# Stepper_Control.net
KiCad netlist of a schematic drawn in EasyEDA
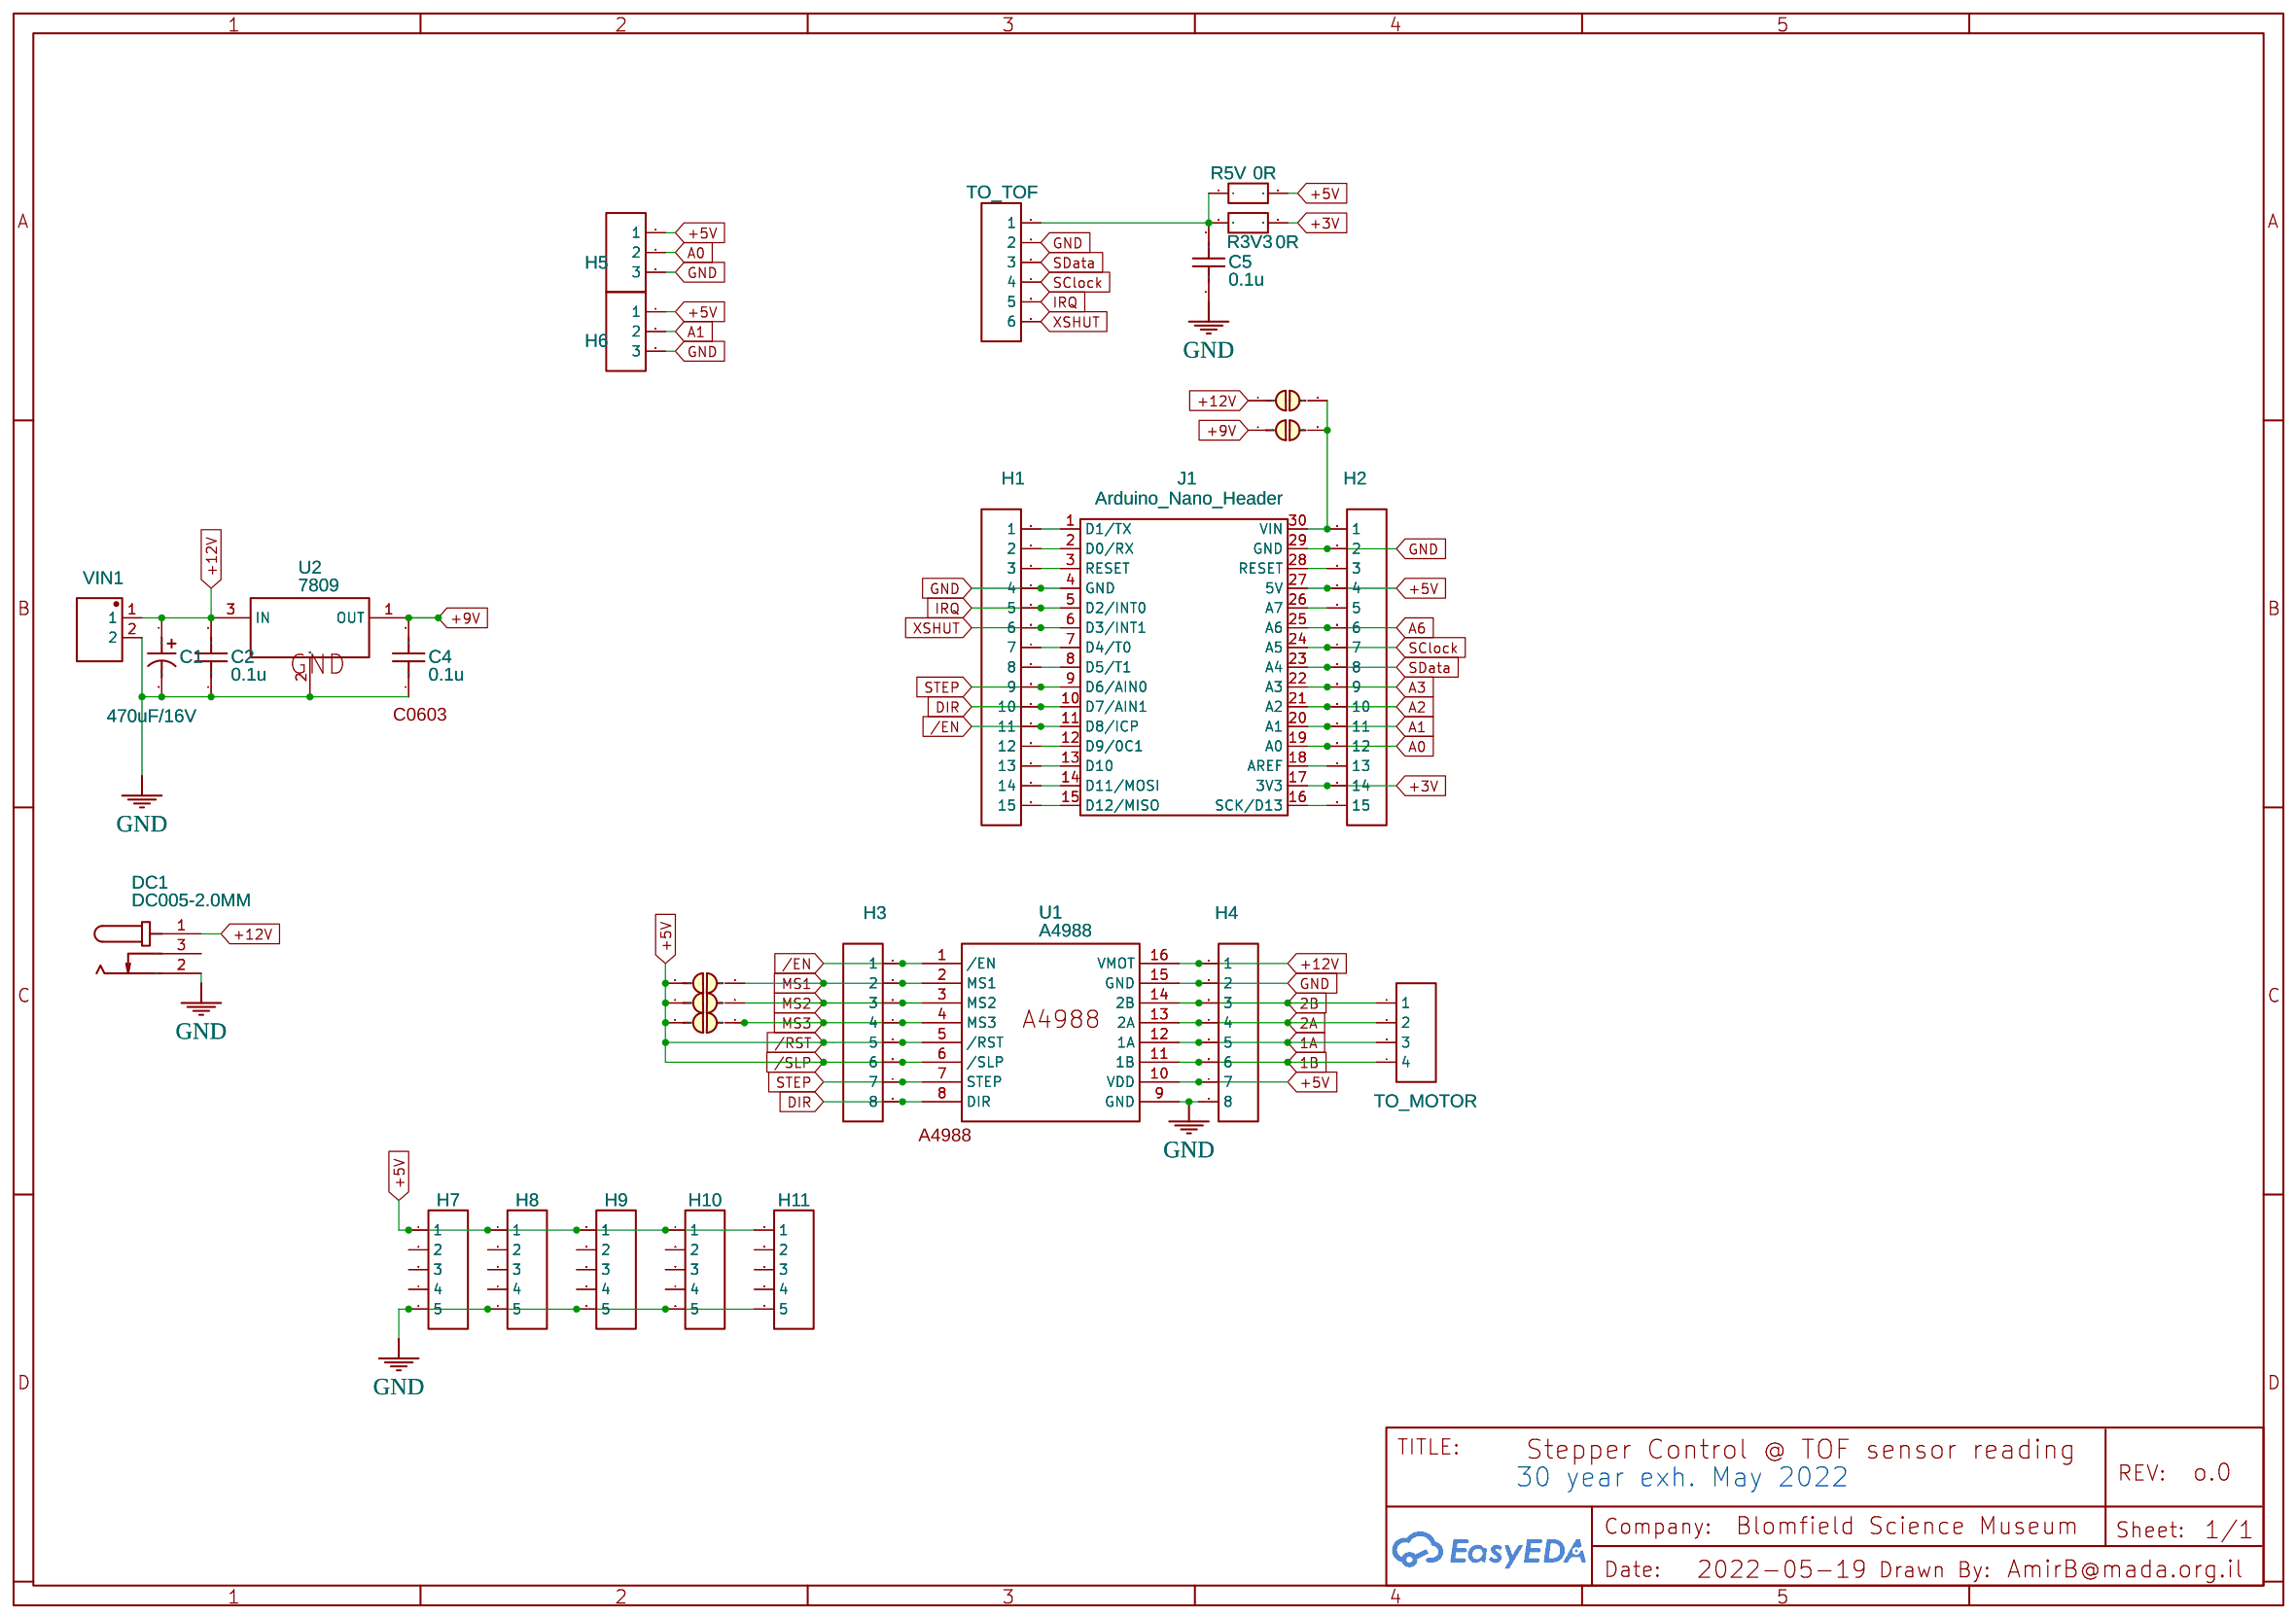
[diagram p0: schematic sheet]

(export (version "E")
  (design (tool "Eeschema 10.0.6"))
  (components
    (comp (ref "C1")
      (value "470uF/16V")
      (fields
        (field (name "BOM_Manufacturer Part") "16V470uF CD110")
        (field (name "BOM_Supplier Part") "C2960230")
      )
      (libsource (lib "") (part "16V470UF CD110"))
    )
    (comp (ref "C2") (value "0.1u") (libsource (lib "") (part "C_0603_US_1")))
    (comp (ref "C4") (value "0.1u") (libsource (lib "") (part "C_0603_US")))
    (comp (ref "C5") (value "0.1u") (libsource (lib "") (part "C_0603_US_1")))
    (comp (ref "DC1")
      (value "DC005-2.0MM")
      (fields (field (name "BOM_Supplier Part") "C111567"))
      (libsource (lib "") (part "DC005-2.0MM"))
    )
    (comp (ref "H1")
      (value "HDR-F-2.54_1x15")
      (fields (field (name "BOM_Supplier Part") "C124408"))
      (libsource (lib "") (part "HDR-F-2.54_1x15_1"))
    )
    (comp (ref "H2")
      (value "HDR-F-2.54_1x15")
      (fields (field (name "BOM_Supplier Part") "C124408"))
      (libsource (lib "") (part "HDR-F-2.54_1x15"))
    )
    (comp (ref "H3")
      (value "HDR-F-2.54_1x8")
      (fields (field (name "BOM_Supplier Part") "C225505"))
      (libsource (lib "") (part "HDR-F-2.54_1x8_1"))
    )
    (comp (ref "H4")
      (value "HDR-F-2.54_1x8")
      (fields (field (name "BOM_Supplier Part") "C225505"))
      (libsource (lib "") (part "HDR-F-2.54_1x8"))
    )
    (comp (ref "H5")
      (value "HDR-F-2.54_1x3")
      (fields (field (name "BOM_Supplier Part") "C146690"))
      (libsource (lib "") (part "HDR-F-2.54_1x3"))
    )
    (comp (ref "H6")
      (value "HDR-F-2.54_1x3")
      (fields (field (name "BOM_Supplier Part") "C146690"))
      (libsource (lib "") (part "HDR-F-2.54_1x3"))
    )
    (comp (ref "H7")
      (value "HDR-F-2.54_1x5")
      (fields (field (name "BOM_Supplier Part") "C50950"))
      (libsource (lib "") (part "HDR-F-2.54_1x5"))
    )
    (comp (ref "H8")
      (value "HDR-F-2.54_1x5")
      (fields (field (name "BOM_Supplier Part") "C50950"))
      (libsource (lib "") (part "HDR-F-2.54_1x5"))
    )
    (comp (ref "H9")
      (value "HDR-F-2.54_1x5")
      (fields (field (name "BOM_Supplier Part") "C50950"))
      (libsource (lib "") (part "HDR-F-2.54_1x5"))
    )
    (comp (ref "H10")
      (value "HDR-F-2.54_1x5")
      (fields (field (name "BOM_Supplier Part") "C50950"))
      (libsource (lib "") (part "HDR-F-2.54_1x5"))
    )
    (comp (ref "H11")
      (value "HDR-F-2.54_1x5")
      (fields (field (name "BOM_Supplier Part") "C50950"))
      (libsource (lib "") (part "HDR-F-2.54_1x5"))
    )
    (comp (ref "J1") (value "Arduino_Nano_Header") (libsource (lib "") (part "Arduino_Nano_Header")))
    (comp (ref "J9V") (value "JUMPER-SMT_2") (libsource (lib "") (part "JUMPER-SMT_2_2")))
    (comp (ref "J12V") (value "JUMPER-SMT_2") (libsource (lib "") (part "JUMPER-SMT_2_1")))
    (comp (ref "JP1") (value "JUMPER-SMT_2") (libsource (lib "") (part "JUMPER-SMT_2")))
    (comp (ref "JP2") (value "JUMPER-SMT_2") (libsource (lib "") (part "JUMPER-SMT_2")))
    (comp (ref "JP3") (value "JUMPER-SMT_2") (libsource (lib "") (part "JUMPER-SMT_2")))
    (comp (ref "R3V3") (value "0R") (libsource (lib "") (part "R_0603_EU")))
    (comp (ref "R5V") (value "0R") (libsource (lib "") (part "R_0603_EU_1")))
    (comp (ref "TO_MOTOR")
      (value "HDR-F-2.54_1x4")
      (fields (field (name "BOM_Supplier Part") "C225501"))
      (libsource (lib "") (part "HDR-F-2.54_1x4"))
    )
    (comp (ref "TO_TOF")
      (value "HDR-F-2.54_1x6")
      (fields (field (name "BOM_Supplier Part") "C40877"))
      (libsource (lib "") (part "HDR-F-2.54_1x6"))
    )
    (comp (ref "U1") (value "A4988") (libsource (lib "") (part "A4988")))
    (comp (ref "U2")
      (value "7809")
      (fields (field (name "BOM_Manufacturer Part") "CJ78L05") (field (name "BOM_Supplier Part") "C2079"))
      (libsource (lib "") (part "7805(SOT-89)"))
    )
    (comp (ref "VIN1")
      (value "640456-2")
      (fields (field (name "BOM_Supplier Part") "C86502"))
      (libsource (lib "") (part "640456-2"))
    )
  )
  (nets
    (net (code "1") (name "+3V") (class "Default")
      (node (ref "H2") (pin "14") (pinfunction "14_14") (pintype "unspecified"))
      (node (ref "J1") (pin "17") (pinfunction "3V3_17") (pintype "unspecified"))
      (node (ref "R3V3") (pin "2") (pinfunction "2_2") (pintype "unspecified"))
    )
    (net (code "2") (name "+5V") (class "Default")
      (node (ref "H10") (pin "1") (pinfunction "1_1") (pintype "unspecified"))
      (node (ref "H11") (pin "1") (pinfunction "1_1") (pintype "unspecified"))
      (node (ref "H2") (pin "4") (pinfunction "4_4") (pintype "unspecified"))
      (node (ref "H3") (pin "5") (pinfunction "5_5") (pintype "unspecified"))
      (node (ref "H3") (pin "6") (pinfunction "6_6") (pintype "unspecified"))
      (node (ref "H4") (pin "7") (pinfunction "7_7") (pintype "unspecified"))
      (node (ref "H5") (pin "1") (pinfunction "1_1") (pintype "input"))
      (node (ref "H6") (pin "1") (pinfunction "1_1") (pintype "input"))
      (node (ref "H7") (pin "1") (pinfunction "1_1") (pintype "unspecified"))
      (node (ref "H8") (pin "1") (pinfunction "1_1") (pintype "unspecified"))
      (node (ref "H9") (pin "1") (pinfunction "1_1") (pintype "unspecified"))
      (node (ref "J1") (pin "27") (pinfunction "5V_27") (pintype "unspecified"))
      (node (ref "JP1") (pin "1") (pinfunction "1_1") (pintype "bidirectional"))
      (node (ref "JP2") (pin "1") (pinfunction "1_1") (pintype "bidirectional"))
      (node (ref "JP3") (pin "1") (pinfunction "1_1") (pintype "bidirectional"))
      (node (ref "R5V") (pin "2") (pinfunction "2_2") (pintype "unspecified"))
      (node (ref "U1") (pin "10") (pinfunction "VDD_10") (pintype "unspecified"))
      (node (ref "U1") (pin "5") (pinfunction "/RST_5") (pintype "unspecified"))
      (node (ref "U1") (pin "6") (pinfunction "/SLP_6") (pintype "unspecified"))
    )
    (net (code "3") (name "+9V") (class "Default")
      (node (ref "C4") (pin "2") (pinfunction "2_2") (pintype "unspecified"))
      (node (ref "J9V") (pin "1") (pinfunction "1_1") (pintype "bidirectional"))
      (node (ref "U2") (pin "1") (pinfunction "OUT_1") (pintype "passive"))
    )
    (net (code "4") (name "+12V") (class "Default")
      (node (ref "C1") (pin "1") (pinfunction "1_1") (pintype "input"))
      (node (ref "C2") (pin "2") (pinfunction "2_2") (pintype "unspecified"))
      (node (ref "DC1") (pin "1") (pinfunction "1_1") (pintype "unspecified"))
      (node (ref "H4") (pin "1") (pinfunction "1_1") (pintype "unspecified"))
      (node (ref "J12V") (pin "1") (pinfunction "1_1") (pintype "bidirectional"))
      (node (ref "U1") (pin "16") (pinfunction "VMOT_16") (pintype "unspecified"))
      (node (ref "U2") (pin "3") (pinfunction "IN_3") (pintype "passive"))
      (node (ref "VIN1") (pin "1") (pinfunction "1_1") (pintype "unspecified"))
    )
    (net (code "5") (name "1A") (class "Default")
      (node (ref "H4") (pin "5") (pinfunction "5_5") (pintype "unspecified"))
      (node (ref "TO_MOTOR") (pin "3") (pinfunction "3_3") (pintype "unspecified"))
      (node (ref "U1") (pin "12") (pinfunction "1A_12") (pintype "unspecified"))
    )
    (net (code "6") (name "1B") (class "Default")
      (node (ref "H4") (pin "6") (pinfunction "6_6") (pintype "unspecified"))
      (node (ref "TO_MOTOR") (pin "4") (pinfunction "4_4") (pintype "unspecified"))
      (node (ref "U1") (pin "11") (pinfunction "1B_11") (pintype "unspecified"))
    )
    (net (code "7") (name "2A") (class "Default")
      (node (ref "H4") (pin "4") (pinfunction "4_4") (pintype "unspecified"))
      (node (ref "TO_MOTOR") (pin "2") (pinfunction "2_2") (pintype "unspecified"))
      (node (ref "U1") (pin "13") (pinfunction "2A_13") (pintype "unspecified"))
    )
    (net (code "8") (name "2B") (class "Default")
      (node (ref "H4") (pin "3") (pinfunction "3_3") (pintype "unspecified"))
      (node (ref "TO_MOTOR") (pin "1") (pinfunction "1_1") (pintype "unspecified"))
      (node (ref "U1") (pin "14") (pinfunction "2B_14") (pintype "unspecified"))
    )
    (net (code "9") (name "A0") (class "Default")
      (node (ref "H2") (pin "12") (pinfunction "12_12") (pintype "unspecified"))
      (node (ref "H5") (pin "2") (pinfunction "2_2") (pintype "input"))
      (node (ref "J1") (pin "19") (pinfunction "A0_19") (pintype "unspecified"))
    )
    (net (code "10") (name "A1") (class "Default")
      (node (ref "H2") (pin "11") (pinfunction "11_11") (pintype "unspecified"))
      (node (ref "H6") (pin "2") (pinfunction "2_2") (pintype "input"))
      (node (ref "J1") (pin "20") (pinfunction "A1_20") (pintype "unspecified"))
    )
    (net (code "11") (name "A2") (class "Default")
      (node (ref "H2") (pin "10") (pinfunction "10_10") (pintype "unspecified"))
      (node (ref "J1") (pin "21") (pinfunction "A2_21") (pintype "unspecified"))
    )
    (net (code "12") (name "A3") (class "Default")
      (node (ref "H2") (pin "9") (pinfunction "9_9") (pintype "unspecified"))
      (node (ref "J1") (pin "22") (pinfunction "A3_22") (pintype "unspecified"))
    )
    (net (code "13") (name "A6") (class "Default")
      (node (ref "H2") (pin "6") (pinfunction "6_6") (pintype "unspecified"))
      (node (ref "J1") (pin "25") (pinfunction "A6_25") (pintype "unspecified"))
    )
    (net (code "14") (name "DIR") (class "Default")
      (node (ref "H1") (pin "10") (pinfunction "10_10") (pintype "unspecified"))
      (node (ref "H3") (pin "8") (pinfunction "8_8") (pintype "unspecified"))
      (node (ref "J1") (pin "10") (pinfunction "D7/AIN1_10") (pintype "unspecified"))
      (node (ref "U1") (pin "8") (pinfunction "DIR_8") (pintype "unspecified"))
    )
    (net (code "15") (name "GND") (class "Default")
      (node (ref "C1") (pin "2") (pinfunction "2_2") (pintype "input"))
      (node (ref "C2") (pin "1") (pinfunction "1_1") (pintype "unspecified"))
      (node (ref "C4") (pin "1") (pinfunction "1_1") (pintype "unspecified"))
      (node (ref "C5") (pin "1") (pinfunction "1_1") (pintype "unspecified"))
      (node (ref "DC1") (pin "2") (pinfunction "2_2") (pintype "unspecified"))
      (node (ref "H1") (pin "4") (pinfunction "4_4") (pintype "unspecified"))
      (node (ref "H10") (pin "5") (pinfunction "5_5") (pintype "unspecified"))
      (node (ref "H11") (pin "5") (pinfunction "5_5") (pintype "unspecified"))
      (node (ref "H2") (pin "2") (pinfunction "2_2") (pintype "unspecified"))
      (node (ref "H4") (pin "2") (pinfunction "2_2") (pintype "unspecified"))
      (node (ref "H4") (pin "8") (pinfunction "8_8") (pintype "unspecified"))
      (node (ref "H5") (pin "3") (pinfunction "3_3") (pintype "input"))
      (node (ref "H6") (pin "3") (pinfunction "3_3") (pintype "input"))
      (node (ref "H7") (pin "5") (pinfunction "5_5") (pintype "unspecified"))
      (node (ref "H8") (pin "5") (pinfunction "5_5") (pintype "unspecified"))
      (node (ref "H9") (pin "5") (pinfunction "5_5") (pintype "unspecified"))
      (node (ref "J1") (pin "29") (pinfunction "GND_29") (pintype "unspecified"))
      (node (ref "J1") (pin "4") (pinfunction "GND_4") (pintype "unspecified"))
      (node (ref "TO_TOF") (pin "2") (pinfunction "2_2") (pintype "input"))
      (node (ref "U1") (pin "15") (pinfunction "GND_15") (pintype "unspecified"))
      (node (ref "U1") (pin "9") (pinfunction "GND_9") (pintype "unspecified"))
      (node (ref "U2") (pin "2") (pinfunction "GND_2") (pintype "passive"))
      (node (ref "VIN1") (pin "2") (pinfunction "2_2") (pintype "unspecified"))
    )
    (net (code "16") (name "IRQ") (class "Default")
      (node (ref "H1") (pin "5") (pinfunction "5_5") (pintype "unspecified"))
      (node (ref "J1") (pin "5") (pinfunction "D2/INT0_5") (pintype "unspecified"))
      (node (ref "TO_TOF") (pin "5") (pinfunction "5_5") (pintype "input"))
    )
    (net (code "17") (name "MS1") (class "Default")
      (node (ref "H3") (pin "2") (pinfunction "2_2") (pintype "unspecified"))
      (node (ref "JP1") (pin "2") (pinfunction "2_2") (pintype "bidirectional"))
      (node (ref "U1") (pin "2") (pinfunction "MS1_2") (pintype "unspecified"))
    )
    (net (code "18") (name "MS2") (class "Default")
      (node (ref "H3") (pin "3") (pinfunction "3_3") (pintype "unspecified"))
      (node (ref "JP2") (pin "2") (pinfunction "2_2") (pintype "bidirectional"))
      (node (ref "U1") (pin "3") (pinfunction "MS2_3") (pintype "unspecified"))
    )
    (net (code "19") (name "MS3") (class "Default")
      (node (ref "H3") (pin "4") (pinfunction "4_4") (pintype "unspecified"))
      (node (ref "JP3") (pin "2") (pinfunction "2_2") (pintype "bidirectional"))
      (node (ref "U1") (pin "4") (pinfunction "MS3_4") (pintype "unspecified"))
    )
    (net (code "20") (name "Net-(C5-Pad2)") (class "Default")
      (node (ref "C5") (pin "2") (pinfunction "2_2") (pintype "unspecified"))
      (node (ref "R3V3") (pin "1") (pinfunction "1_1") (pintype "unspecified"))
      (node (ref "R5V") (pin "1") (pinfunction "1_1") (pintype "unspecified"))
      (node (ref "TO_TOF") (pin "1") (pinfunction "1_1") (pintype "input"))
    )
    (net (code "21") (name "Net-(H1-Pad3)") (class "Default")
      (node (ref "H1") (pin "3") (pinfunction "3_3") (pintype "unspecified"))
      (node (ref "J1") (pin "3") (pinfunction "RESET_3") (pintype "unspecified"))
    )
    (net (code "22") (name "Net-(H2-Pad3)") (class "Default")
      (node (ref "H2") (pin "3") (pinfunction "3_3") (pintype "unspecified"))
      (node (ref "J1") (pin "28") (pinfunction "RESET_28") (pintype "unspecified"))
    )
    (net (code "23") (name "Net-(J1-A7)") (class "Default")
      (node (ref "H2") (pin "5") (pinfunction "5_5") (pintype "unspecified"))
      (node (ref "J1") (pin "26") (pinfunction "A7_26") (pintype "unspecified"))
    )
    (net (code "24") (name "Net-(J1-AREF)") (class "Default")
      (node (ref "H2") (pin "13") (pinfunction "13_13") (pintype "unspecified"))
      (node (ref "J1") (pin "18") (pinfunction "AREF_18") (pintype "unspecified"))
    )
    (net (code "25") (name "Net-(J1-D0{slash}RX)") (class "Default")
      (node (ref "H1") (pin "2") (pinfunction "2_2") (pintype "unspecified"))
      (node (ref "J1") (pin "2") (pinfunction "D0/RX_2") (pintype "unspecified"))
    )
    (net (code "26") (name "Net-(J1-D1{slash}TX)") (class "Default")
      (node (ref "H1") (pin "1") (pinfunction "1_1") (pintype "unspecified"))
      (node (ref "J1") (pin "1") (pinfunction "D1/TX_1") (pintype "unspecified"))
    )
    (net (code "27") (name "Net-(J1-D4{slash}T0)") (class "Default")
      (node (ref "H1") (pin "7") (pinfunction "7_7") (pintype "unspecified"))
      (node (ref "J1") (pin "7") (pinfunction "D4/T0_7") (pintype "unspecified"))
    )
    (net (code "28") (name "Net-(J1-D5{slash}T1)") (class "Default")
      (node (ref "H1") (pin "8") (pinfunction "8_8") (pintype "unspecified"))
      (node (ref "J1") (pin "8") (pinfunction "D5/T1_8") (pintype "unspecified"))
    )
    (net (code "29") (name "Net-(J1-D9{slash}0C1)") (class "Default")
      (node (ref "H1") (pin "12") (pinfunction "12_12") (pintype "unspecified"))
      (node (ref "J1") (pin "12") (pinfunction "D9/0C1_12") (pintype "unspecified"))
    )
    (net (code "30") (name "Net-(J1-D10)") (class "Default")
      (node (ref "H1") (pin "13") (pinfunction "13_13") (pintype "unspecified"))
      (node (ref "J1") (pin "13") (pinfunction "D10_13") (pintype "unspecified"))
    )
    (net (code "31") (name "Net-(J1-D11{slash}MOSI)") (class "Default")
      (node (ref "H1") (pin "14") (pinfunction "14_14") (pintype "unspecified"))
      (node (ref "J1") (pin "14") (pinfunction "D11/MOSI_14") (pintype "unspecified"))
    )
    (net (code "32") (name "Net-(J1-D12{slash}MISO)") (class "Default")
      (node (ref "H1") (pin "15") (pinfunction "15_15") (pintype "unspecified"))
      (node (ref "J1") (pin "15") (pinfunction "D12/MISO_15") (pintype "unspecified"))
    )
    (net (code "33") (name "Net-(J1-SCK{slash}D13)") (class "Default")
      (node (ref "H2") (pin "15") (pinfunction "15_15") (pintype "unspecified"))
      (node (ref "J1") (pin "16") (pinfunction "SCK/D13_16") (pintype "unspecified"))
    )
    (net (code "34") (name "Net-(J1-VIN)") (class "Default")
      (node (ref "H2") (pin "1") (pinfunction "1_1") (pintype "unspecified"))
      (node (ref "J1") (pin "30") (pinfunction "VIN_30") (pintype "unspecified"))
      (node (ref "J12V") (pin "2") (pinfunction "2_2") (pintype "bidirectional"))
      (node (ref "J9V") (pin "2") (pinfunction "2_2") (pintype "bidirectional"))
    )
    (net (code "35") (name "SClock") (class "Default")
      (node (ref "H2") (pin "7") (pinfunction "7_7") (pintype "unspecified"))
      (node (ref "J1") (pin "24") (pinfunction "A5_24") (pintype "unspecified"))
      (node (ref "TO_TOF") (pin "4") (pinfunction "4_4") (pintype "input"))
    )
    (net (code "36") (name "SData") (class "Default")
      (node (ref "H2") (pin "8") (pinfunction "8_8") (pintype "unspecified"))
      (node (ref "J1") (pin "23") (pinfunction "A4_23") (pintype "unspecified"))
      (node (ref "TO_TOF") (pin "3") (pinfunction "3_3") (pintype "input"))
    )
    (net (code "37") (name "STEP") (class "Default")
      (node (ref "H1") (pin "9") (pinfunction "9_9") (pintype "unspecified"))
      (node (ref "H3") (pin "7") (pinfunction "7_7") (pintype "unspecified"))
      (node (ref "J1") (pin "9") (pinfunction "D6/AIN0_9") (pintype "unspecified"))
      (node (ref "U1") (pin "7") (pinfunction "STEP_7") (pintype "unspecified"))
    )
    (net (code "38") (name "XSHUT") (class "Default")
      (node (ref "H1") (pin "6") (pinfunction "6_6") (pintype "unspecified"))
      (node (ref "J1") (pin "6") (pinfunction "D3/INT1_6") (pintype "unspecified"))
      (node (ref "TO_TOF") (pin "6") (pinfunction "6_6") (pintype "input"))
    )
    (net (code "39") (name "unconnected-(DC1-Pad3)") (class "Default")
      (node (ref "DC1") (pin "3") (pinfunction "3_3") (pintype "unspecified"))
    )
    (net (code "40") (name "unconnected-(H7-Pad2)") (class "Default")
      (node (ref "H7") (pin "2") (pinfunction "2_2") (pintype "unspecified"))
    )
    (net (code "41") (name "unconnected-(H7-Pad3)") (class "Default")
      (node (ref "H7") (pin "3") (pinfunction "3_3") (pintype "unspecified"))
    )
    (net (code "42") (name "unconnected-(H7-Pad4)") (class "Default")
      (node (ref "H7") (pin "4") (pinfunction "4_4") (pintype "unspecified"))
    )
    (net (code "43") (name "unconnected-(H8-Pad2)") (class "Default")
      (node (ref "H8") (pin "2") (pinfunction "2_2") (pintype "unspecified"))
    )
    (net (code "44") (name "unconnected-(H8-Pad3)") (class "Default")
      (node (ref "H8") (pin "3") (pinfunction "3_3") (pintype "unspecified"))
    )
    (net (code "45") (name "unconnected-(H8-Pad4)") (class "Default")
      (node (ref "H8") (pin "4") (pinfunction "4_4") (pintype "unspecified"))
    )
    (net (code "46") (name "unconnected-(H9-Pad2)") (class "Default")
      (node (ref "H9") (pin "2") (pinfunction "2_2") (pintype "unspecified"))
    )
    (net (code "47") (name "unconnected-(H9-Pad3)") (class "Default")
      (node (ref "H9") (pin "3") (pinfunction "3_3") (pintype "unspecified"))
    )
    (net (code "48") (name "unconnected-(H9-Pad4)") (class "Default")
      (node (ref "H9") (pin "4") (pinfunction "4_4") (pintype "unspecified"))
    )
    (net (code "49") (name "unconnected-(H10-Pad2)") (class "Default")
      (node (ref "H10") (pin "2") (pinfunction "2_2") (pintype "unspecified"))
    )
    (net (code "50") (name "unconnected-(H10-Pad3)") (class "Default")
      (node (ref "H10") (pin "3") (pinfunction "3_3") (pintype "unspecified"))
    )
    (net (code "51") (name "unconnected-(H10-Pad4)") (class "Default")
      (node (ref "H10") (pin "4") (pinfunction "4_4") (pintype "unspecified"))
    )
    (net (code "52") (name "unconnected-(H11-Pad2)") (class "Default")
      (node (ref "H11") (pin "2") (pinfunction "2_2") (pintype "unspecified"))
    )
    (net (code "53") (name "unconnected-(H11-Pad3)") (class "Default")
      (node (ref "H11") (pin "3") (pinfunction "3_3") (pintype "unspecified"))
    )
    (net (code "54") (name "unconnected-(H11-Pad4)") (class "Default")
      (node (ref "H11") (pin "4") (pinfunction "4_4") (pintype "unspecified"))
    )
    (net (code "55") (name "{slash}EN") (class "Default")
      (node (ref "H1") (pin "11") (pinfunction "11_11") (pintype "unspecified"))
      (node (ref "H3") (pin "1") (pinfunction "1_1") (pintype "unspecified"))
      (node (ref "J1") (pin "11") (pinfunction "D8/ICP_11") (pintype "unspecified"))
      (node (ref "U1") (pin "1") (pinfunction "/EN_1") (pintype "unspecified"))
    )
  )
)
